# DC309A_FTDI.net
KiCad netlist of a schematic drawn in Altium Designer
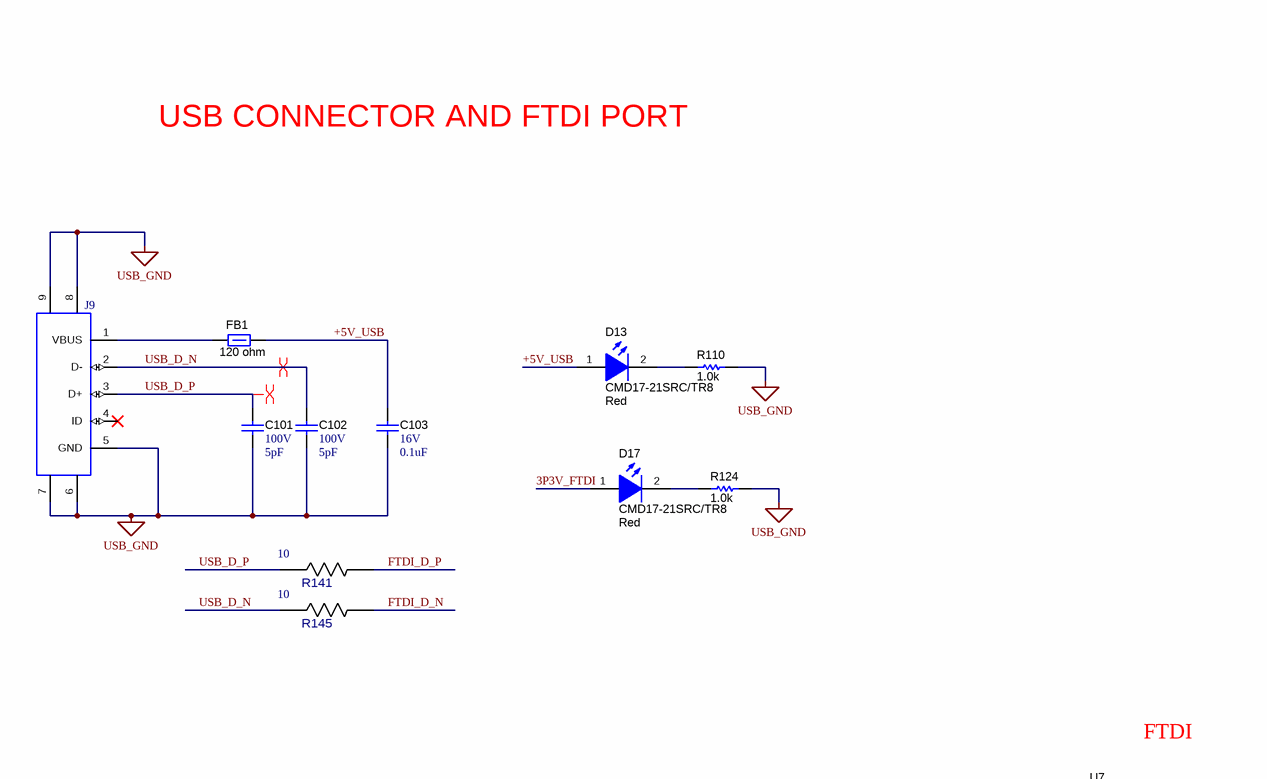
[diagram p0: DC309A_FTDI.SchDoc, top left]
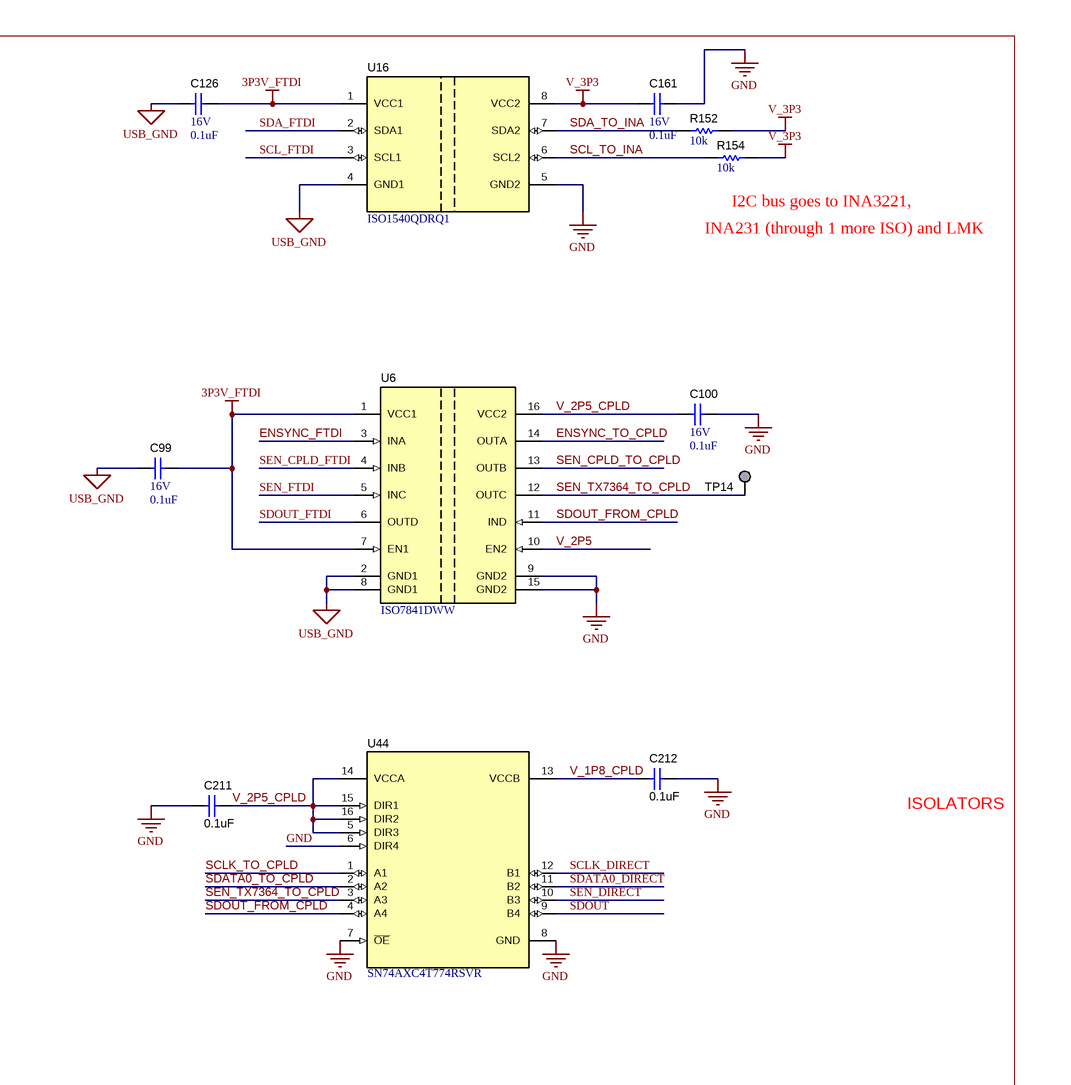
[diagram p1: DC309A_FTDI.SchDoc, top right]
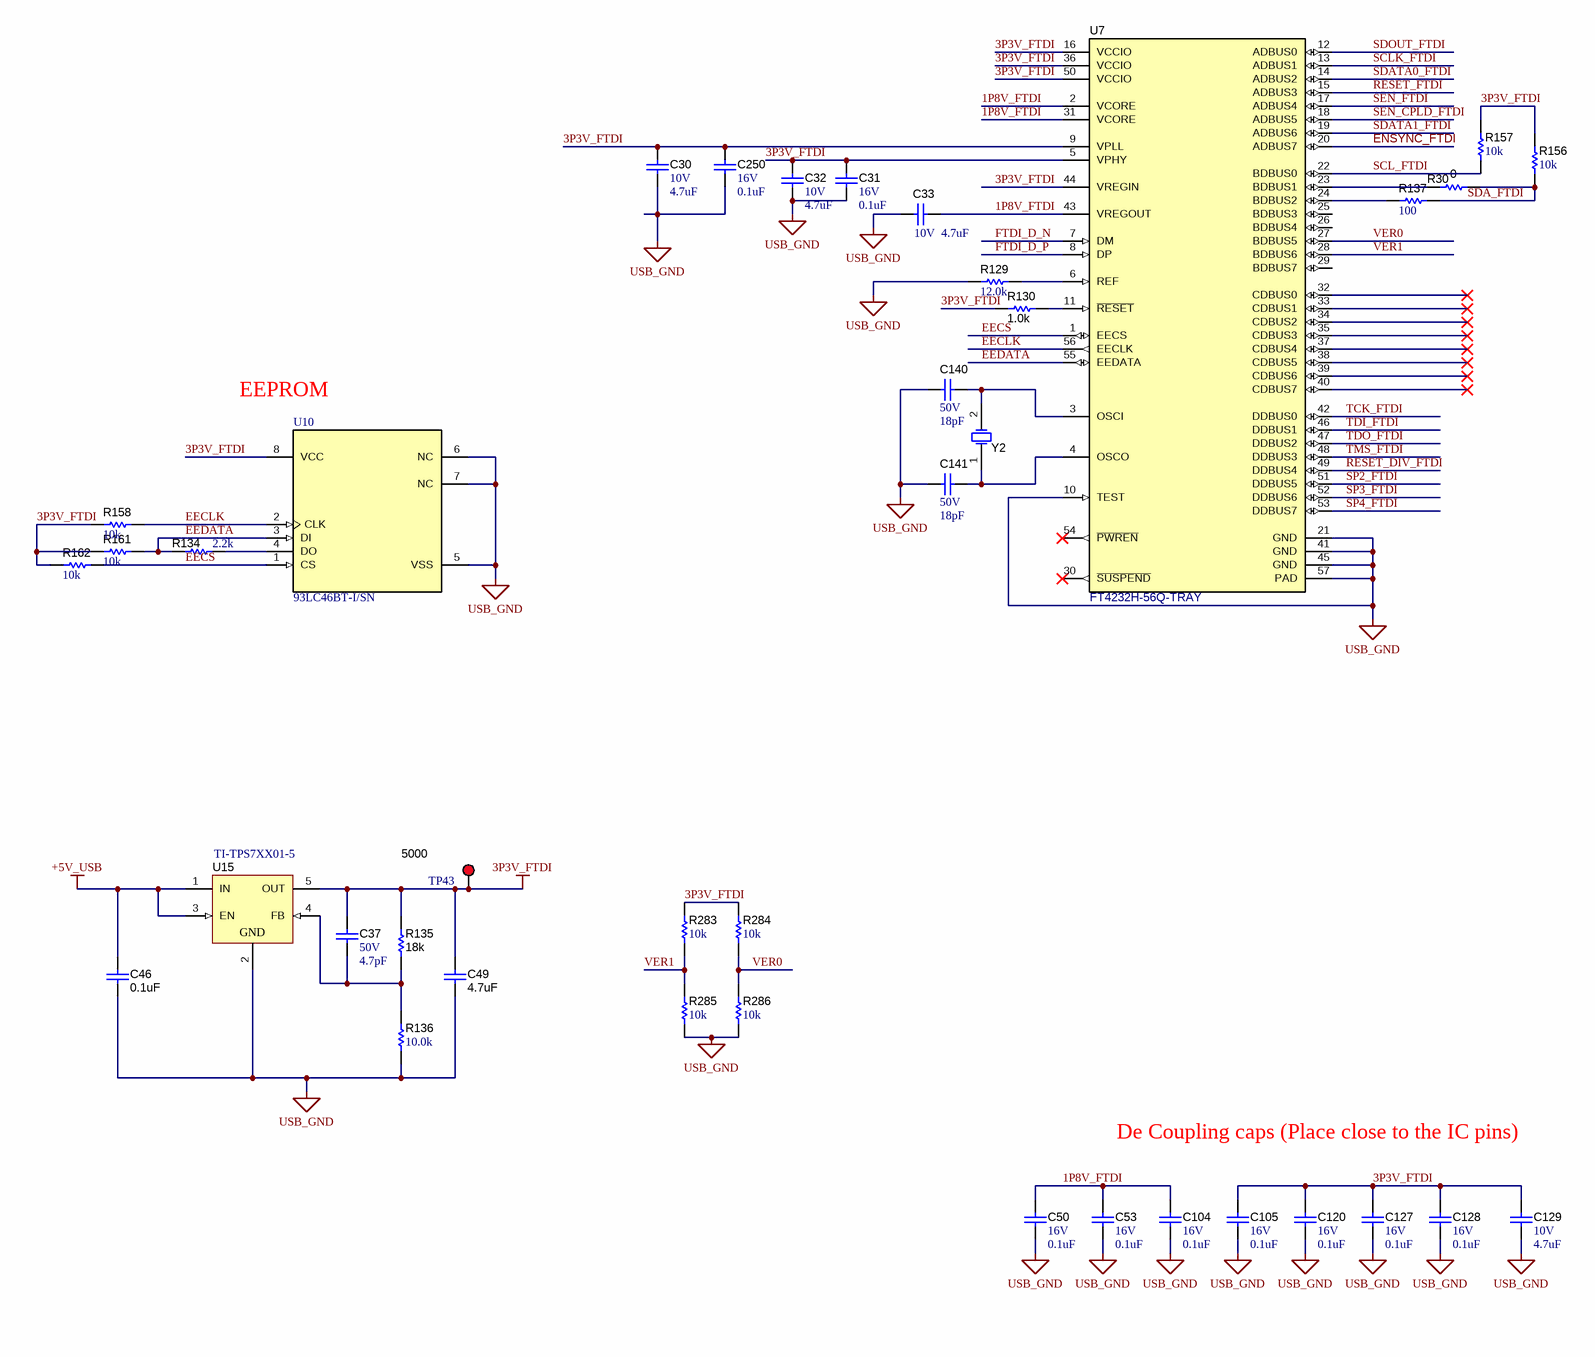
[diagram p2: DC309A_FTDI.SchDoc, bottom left]
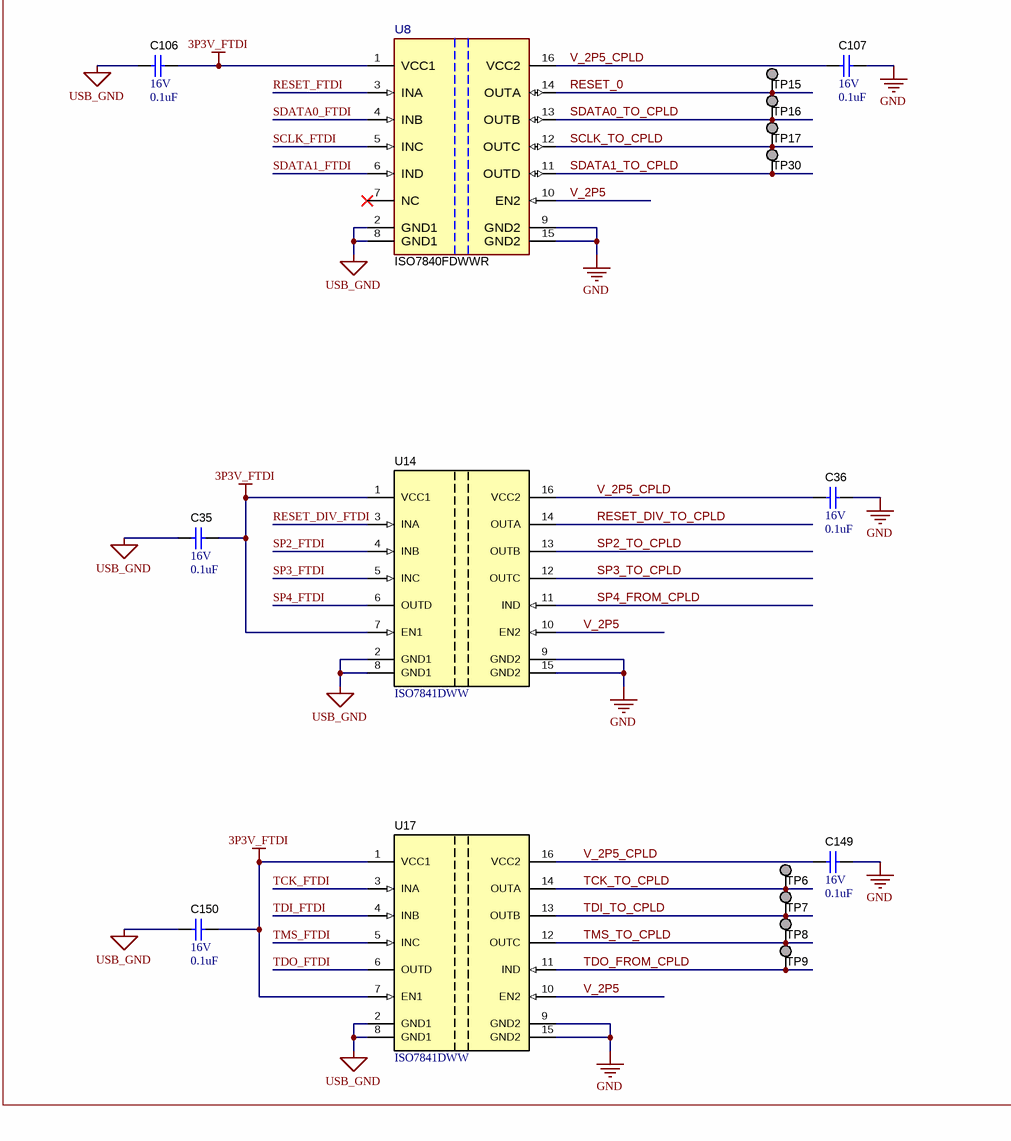
[diagram p3: DC309A_FTDI.SchDoc, bottom right]

(export (version "E")
  (design (tool "Eeschema 10.0.6"))
  (components
    (comp (ref "C30")
      (value "CL05A475MP5NRNC")
      (footprint "0402")
      (description "CAP, CERM, 4.7 uF, 10 V, +/- 20%, X5R, 0402")
      (fields
        (field (name "MANUFACTURER") "Samsung Electro-Mechanics")
        (field (name "VDC_V") "10V")
        (field (name "VALUEDISPLAYED") "4.7uF")
        (field (name "PUBLISHER") "Texas Instruments")
      )
      (libsource (lib "Altium Vault - TI") (part "Capacitor"))
    )
    (comp (ref "C31")
      (value "0402YC104KAT2A")
      (footprint "0402")
      (description "CAP, CERM, 0.1 uF, 16 V, +/- 10%, X7R, 0402")
      (fields
        (field (name "MANUFACTURER") "AVX")
        (field (name "VDC_V") "16V")
        (field (name "VALUEDISPLAYED") "0.1uF")
        (field (name "PUBLISHER") "Texas Instruments")
      )
      (libsource (lib "Altium Vault - TI") (part "Capacitor"))
    )
    (comp (ref "C32")
      (value "CL05A475MP5NRNC")
      (footprint "0402")
      (description "CAP, CERM, 4.7 uF, 10 V, +/- 20%, X5R, 0402")
      (fields
        (field (name "MANUFACTURER") "Samsung Electro-Mechanics")
        (field (name "VDC_V") "10V")
        (field (name "VALUEDISPLAYED") "4.7uF")
        (field (name "PUBLISHER") "Texas Instruments")
      )
      (libsource (lib "Altium Vault - TI") (part "Capacitor"))
    )
    (comp (ref "C33")
      (value "CL05A475MP5NRNC")
      (footprint "0402")
      (description "CAP, CERM, 4.7 uF, 10 V, +/- 20%, X5R, 0402")
      (fields
        (field (name "MANUFACTURER") "Samsung Electro-Mechanics")
        (field (name "VDC_V") "10V")
        (field (name "VALUEDISPLAYED") "4.7uF")
        (field (name "PUBLISHER") "Texas Instruments")
      )
      (libsource (lib "Altium Vault - TI") (part "Capacitor"))
    )
    (comp (ref "C35")
      (value "0402YC104KAT2A")
      (footprint "0402")
      (description "CAP, CERM, 0.1 uF, 16 V, +/- 10%, X7R, 0402")
      (fields
        (field (name "MANUFACTURER") "AVX")
        (field (name "VDC_V") "16V")
        (field (name "VALUEDISPLAYED") "0.1uF")
        (field (name "PUBLISHER") "Texas Instruments")
      )
      (libsource (lib "Altium Vault - TI") (part "Capacitor"))
    )
    (comp (ref "C36")
      (value "0402YC104KAT2A")
      (footprint "0402")
      (description "CAP, CERM, 0.1 uF, 16 V, +/- 10%, X7R, 0402")
      (fields
        (field (name "MANUFACTURER") "AVX")
        (field (name "VDC_V") "16V")
        (field (name "VALUEDISPLAYED") "0.1uF")
        (field (name "PUBLISHER") "Texas Instruments")
      )
      (libsource (lib "Altium Vault - TI") (part "Capacitor"))
    )
    (comp (ref "C37")
      (value "06035A4R7CAT2A")
      (footprint "0603")
      (description "CAP, CERM, 4.7 pF, 50 V, +/- 5%, C0G/NP0, 0603")
      (fields
        (field (name "MANUFACTURER") "AVX")
        (field (name "VDC_V") "50V")
        (field (name "VALUEDISPLAYED") "4.7pF")
        (field (name "PUBLISHER") "Texas Instruments")
      )
      (libsource (lib "Altium Vault - TI") (part "Capacitor"))
    )
    (comp (ref "C46")
      (value "Capacitor")
      (footprint "0402")
      (description "CAP, CERM, 0.1 uF, 16 V, +/- 10%, X7R, 0402")
      (fields
        (field (name "PARTNUMBER") "0402YC104KAT2A")
        (field (name "VALUEDISPLAYED") "0.1uF")
        (field (name "MANUFACTURER") "AVX")
        (field (name "PUBLISHER") "Texas Instruments")
      )
      (libsource (lib "Altium Vault - TI") (part "Capacitor"))
    )
    (comp (ref "C49")
      (value "Capacitor")
      (footprint "0805_HV")
      (description "CAP, CERM, 4.7 uF, 25 V, +/- 10%, X5R, 0805")
      (fields
        (field (name "PARTNUMBER") "C0805C475K3PACTU")
        (field (name "VALUEDISPLAYED") "4.7uF")
        (field (name "MANUFACTURER") "Kemet")
        (field (name "PUBLISHER") "Texas Instruments")
      )
      (libsource (lib "Altium Vault - TI") (part "CMP-0007800-2"))
    )
    (comp (ref "C50")
      (value "0402YC104KAT2A")
      (footprint "0402")
      (description "CAP, CERM, 0.1 uF, 16 V, +/- 10%, X7R, 0402")
      (fields
        (field (name "MANUFACTURER") "AVX")
        (field (name "VDC_V") "16V")
        (field (name "VALUEDISPLAYED") "0.1uF")
        (field (name "PUBLISHER") "Texas Instruments")
      )
      (libsource (lib "Altium Vault - TI") (part "Capacitor"))
    )
    (comp (ref "C53")
      (value "0402YC104KAT2A")
      (footprint "0402")
      (description "CAP, CERM, 0.1 uF, 16 V, +/- 10%, X7R, 0402")
      (fields
        (field (name "MANUFACTURER") "AVX")
        (field (name "VDC_V") "16V")
        (field (name "VALUEDISPLAYED") "0.1uF")
        (field (name "PUBLISHER") "Texas Instruments")
      )
      (libsource (lib "Altium Vault - TI") (part "Capacitor"))
    )
    (comp (ref "C99")
      (value "0402YC104KAT2A")
      (footprint "0402")
      (description "CAP, CERM, 0.1 uF, 16 V, +/- 10%, X7R, 0402")
      (fields
        (field (name "MANUFACTURER") "AVX")
        (field (name "VDC_V") "16V")
        (field (name "VALUEDISPLAYED") "0.1uF")
        (field (name "PUBLISHER") "Texas Instruments")
      )
      (libsource (lib "Altium Vault - TI") (part "Capacitor"))
    )
    (comp (ref "C100")
      (value "0402YC104KAT2A")
      (footprint "0402")
      (description "CAP, CERM, 0.1 uF, 16 V, +/- 10%, X7R, 0402")
      (fields
        (field (name "MANUFACTURER") "AVX")
        (field (name "VDC_V") "16V")
        (field (name "VALUEDISPLAYED") "0.1uF")
        (field (name "PUBLISHER") "Texas Instruments")
      )
      (libsource (lib "Altium Vault - TI") (part "Capacitor"))
    )
    (comp (ref "C101")
      (value "CBR04C509B1GAC")
      (footprint "0402")
      (description "CAP, CERM, 5 pF, 100 V,+/- 2%, C0G/NP0, 0402")
      (fields
        (field (name "MANUFACTURER") "Kemet")
        (field (name "VDC_V") "100V")
        (field (name "VALUEDISPLAYED") "5pF")
      )
      (libsource (lib "Altium Vault - TI") (part "Capacitor"))
    )
    (comp (ref "C102")
      (value "CBR04C509B1GAC")
      (footprint "0402")
      (description "CAP, CERM, 5 pF, 100 V,+/- 2%, C0G/NP0, 0402")
      (fields
        (field (name "MANUFACTURER") "Kemet")
        (field (name "VDC_V") "100V")
        (field (name "VALUEDISPLAYED") "5pF")
      )
      (libsource (lib "Altium Vault - TI") (part "Capacitor"))
    )
    (comp (ref "C103")
      (value "0402YC104KAT2A")
      (footprint "0402")
      (description "CAP, CERM, 0.1 uF, 16 V, +/- 10%, X7R, 0402")
      (fields
        (field (name "MANUFACTURER") "AVX")
        (field (name "VDC_V") "16V")
        (field (name "VALUEDISPLAYED") "0.1uF")
        (field (name "PUBLISHER") "Texas Instruments")
      )
      (libsource (lib "Altium Vault - TI") (part "Capacitor"))
    )
    (comp (ref "C104")
      (value "0402YC104KAT2A")
      (footprint "0402")
      (description "CAP, CERM, 0.1 uF, 16 V, +/- 10%, X7R, 0402")
      (fields
        (field (name "MANUFACTURER") "AVX")
        (field (name "VDC_V") "16V")
        (field (name "VALUEDISPLAYED") "0.1uF")
        (field (name "PUBLISHER") "Texas Instruments")
      )
      (libsource (lib "Altium Vault - TI") (part "Capacitor"))
    )
    (comp (ref "C105")
      (value "0402YC104KAT2A")
      (footprint "0402")
      (description "CAP, CERM, 0.1 uF, 16 V, +/- 10%, X7R, 0402")
      (fields
        (field (name "MANUFACTURER") "AVX")
        (field (name "VDC_V") "16V")
        (field (name "VALUEDISPLAYED") "0.1uF")
        (field (name "PUBLISHER") "Texas Instruments")
      )
      (libsource (lib "Altium Vault - TI") (part "Capacitor"))
    )
    (comp (ref "C106")
      (value "0402YC104KAT2A")
      (footprint "0402")
      (description "CAP, CERM, 0.1 uF, 16 V, +/- 10%, X7R, 0402")
      (fields
        (field (name "MANUFACTURER") "AVX")
        (field (name "VDC_V") "16V")
        (field (name "VALUEDISPLAYED") "0.1uF")
        (field (name "PUBLISHER") "Texas Instruments")
      )
      (libsource (lib "Altium Vault - TI") (part "Capacitor"))
    )
    (comp (ref "C107")
      (value "0402YC104KAT2A")
      (footprint "0402")
      (description "CAP, CERM, 0.1 uF, 16 V, +/- 10%, X7R, 0402")
      (fields
        (field (name "MANUFACTURER") "AVX")
        (field (name "VDC_V") "16V")
        (field (name "VALUEDISPLAYED") "0.1uF")
        (field (name "PUBLISHER") "Texas Instruments")
      )
      (libsource (lib "Altium Vault - TI") (part "Capacitor"))
    )
    (comp (ref "C120")
      (value "0402YC104KAT2A")
      (footprint "0402")
      (description "CAP, CERM, 0.1 uF, 16 V, +/- 10%, X7R, 0402")
      (fields
        (field (name "MANUFACTURER") "AVX")
        (field (name "VDC_V") "16V")
        (field (name "VALUEDISPLAYED") "0.1uF")
        (field (name "PUBLISHER") "Texas Instruments")
      )
      (libsource (lib "Altium Vault - TI") (part "Capacitor"))
    )
    (comp (ref "C126")
      (value "0402YC104KAT2A")
      (footprint "0402")
      (description "CAP, CERM, 0.1 uF, 16 V, +/- 10%, X7R, 0402")
      (fields
        (field (name "MANUFACTURER") "AVX")
        (field (name "VDC_V") "16V")
        (field (name "VALUEDISPLAYED") "0.1uF")
        (field (name "PUBLISHER") "Texas Instruments")
      )
      (libsource (lib "Altium Vault - TI") (part "Capacitor"))
    )
    (comp (ref "C127")
      (value "0402YC104KAT2A")
      (footprint "0402")
      (description "CAP, CERM, 0.1 uF, 16 V, +/- 10%, X7R, 0402")
      (fields
        (field (name "MANUFACTURER") "AVX")
        (field (name "VDC_V") "16V")
        (field (name "VALUEDISPLAYED") "0.1uF")
        (field (name "PUBLISHER") "Texas Instruments")
      )
      (libsource (lib "Altium Vault - TI") (part "Capacitor"))
    )
    (comp (ref "C128")
      (value "0402YC104KAT2A")
      (footprint "0402")
      (description "CAP, CERM, 0.1 uF, 16 V, +/- 10%, X7R, 0402")
      (fields
        (field (name "MANUFACTURER") "AVX")
        (field (name "VDC_V") "16V")
        (field (name "VALUEDISPLAYED") "0.1uF")
        (field (name "PUBLISHER") "Texas Instruments")
      )
      (libsource (lib "Altium Vault - TI") (part "Capacitor"))
    )
    (comp (ref "C129")
      (value "CL05A475MP5NRNC")
      (footprint "0402")
      (description "CAP, CERM, 4.7 uF, 10 V, +/- 20%, X5R, 0402")
      (fields
        (field (name "MANUFACTURER") "Samsung Electro-Mechanics")
        (field (name "VDC_V") "10V")
        (field (name "VALUEDISPLAYED") "4.7uF")
        (field (name "PUBLISHER") "Texas Instruments")
      )
      (libsource (lib "Altium Vault - TI") (part "Capacitor"))
    )
    (comp (ref "C140")
      (value "06035A180JAT2A")
      (footprint "0603")
      (description "CAP, CERM, 18 pF, 50 V, +/- 5%, C0G/NP0, 0603")
      (fields
        (field (name "MANUFACTURER") "AVX")
        (field (name "VDC_V") "50V")
        (field (name "VALUEDISPLAYED") "18pF")
        (field (name "PUBLISHER") "Texas Instruments")
      )
      (libsource (lib "Altium Vault - TI") (part "Capacitor"))
    )
    (comp (ref "C141")
      (value "06035A180JAT2A")
      (footprint "0603")
      (description "CAP, CERM, 18 pF, 50 V, +/- 5%, C0G/NP0, 0603")
      (fields
        (field (name "MANUFACTURER") "AVX")
        (field (name "VDC_V") "50V")
        (field (name "VALUEDISPLAYED") "18pF")
        (field (name "PUBLISHER") "Texas Instruments")
      )
      (libsource (lib "Altium Vault - TI") (part "Capacitor"))
    )
    (comp (ref "C149")
      (value "0402YC104KAT2A")
      (footprint "0402")
      (description "CAP, CERM, 0.1 uF, 16 V, +/- 10%, X7R, 0402")
      (fields
        (field (name "MANUFACTURER") "AVX")
        (field (name "VDC_V") "16V")
        (field (name "VALUEDISPLAYED") "0.1uF")
        (field (name "PUBLISHER") "Texas Instruments")
      )
      (libsource (lib "Altium Vault - TI") (part "Capacitor"))
    )
    (comp (ref "C150")
      (value "0402YC104KAT2A")
      (footprint "0402")
      (description "CAP, CERM, 0.1 uF, 16 V, +/- 10%, X7R, 0402")
      (fields
        (field (name "MANUFACTURER") "AVX")
        (field (name "VDC_V") "16V")
        (field (name "VALUEDISPLAYED") "0.1uF")
        (field (name "PUBLISHER") "Texas Instruments")
      )
      (libsource (lib "Altium Vault - TI") (part "Capacitor"))
    )
    (comp (ref "C161")
      (value "0402YC104KAT2A")
      (footprint "0402")
      (description "CAP, CERM, 0.1 uF, 16 V, +/- 10%, X7R, 0402")
      (fields
        (field (name "MANUFACTURER") "AVX")
        (field (name "VDC_V") "16V")
        (field (name "VALUEDISPLAYED") "0.1uF")
        (field (name "PUBLISHER") "Texas Instruments")
      )
      (libsource (lib "Altium Vault - TI") (part "Capacitor"))
    )
    (comp (ref "C211")
      (value "0.1uF")
      (footprint "0402")
      (description "CAP, CERM, 0.1 uF, 16 V, +/- 10%, X7R, 0402")
      (fields
        (field (name "PARTNUMBER") "GRM155R71C104KA88D")
        (field (name "MANUFACTURER") "MuRata")
        (field (name "PUBLISHER") "Texas Instruments")
      )
      (libsource (lib "Altium Vault - TI") (part "Capacitor"))
    )
    (comp (ref "C212")
      (value "0.1uF")
      (footprint "0402")
      (description "CAP, CERM, 0.1 uF, 16 V, +/- 10%, X7R, 0402")
      (fields
        (field (name "PARTNUMBER") "GRM155R71C104KA88D")
        (field (name "MANUFACTURER") "MuRata")
        (field (name "PUBLISHER") "Texas Instruments")
      )
      (libsource (lib "Altium Vault - TI") (part "Capacitor"))
    )
    (comp (ref "C250")
      (value "0402YC104KAT2A")
      (footprint "0402")
      (description "CAP, CERM, 0.1 uF, 16 V, +/- 10%, X7R, 0402")
      (fields
        (field (name "MANUFACTURER") "AVX")
        (field (name "VDC_V") "16V")
        (field (name "VALUEDISPLAYED") "0.1uF")
        (field (name "PUBLISHER") "Texas Instruments")
      )
      (libsource (lib "Altium Vault - TI") (part "Capacitor"))
    )
    (comp (ref "D13")
      (value "CMD17-21SRC/TR8")
      (footprint "CMD17-21_Red")
      (description "LED, Red, SMD")
      (fields
        (field (name "ALTIUM_VALUE") "Red")
        (field (name "MANUFACTURER") "Visual Communications Company, LLC")
      )
      (libsource (lib "Altium Vault - TI") (part "LED"))
    )
    (comp (ref "D17")
      (value "CMD17-21SRC/TR8")
      (footprint "CMD17-21_Red")
      (description "LED, Red, SMD")
      (fields
        (field (name "ALTIUM_VALUE") "Red")
        (field (name "MANUFACTURER") "Visual Communications Company, LLC")
      )
      (libsource (lib "Altium Vault - TI") (part "LED"))
    )
    (comp (ref "FB1")
      (value "120 ohm")
      (footprint "0603")
      (description "Ferrite Bead, 120 ohm @ 100 MHz, 3 A, 0603")
      (fields
        (field (name "PARTNUMBER") "BLM18SG121TN1D")
        (field (name "MANUFACTURER") "MuRata")
        (field (name "PUBLISHER") "Texas Instruments")
      )
      (libsource (lib "Altium Vault - TI") (part "Ferrite_Bead"))
    )
    (comp (ref "J9")
      (value "CONN_USB_MINI-AB_4Shld")
      (footprint "Molex_67803-8020")
      (description "Connector, Receptacle, USB - mini AB, R/A, SMD")
      (fields
        (field (name "PARTNUMBER") "67803-8020")
        (field (name "MANUFACTURER") "Molex")
        (field (name "PUBLISHER") "Texas Instruments")
      )
      (libsource (lib "Altium Vault - TI") (part "CONN_USB_MINI-AB_4Shld"))
    )
    (comp (ref "R30")
      (value "0")
      (footprint "0402")
      (description "RES, 0, 5%, 0.1 W, AEC-Q200 Grade 0, 0402")
      (fields (field (name "PARTNUMBER") "ERJ-2GE0R00X") (field (name "MANUFACTURER") "Panasonic"))
      (libsource (lib "Altium Vault - TI") (part "CMP-0026992-3"))
    )
    (comp (ref "R110")
      (value "Resistor")
      (footprint "0402")
      (description "RES, 1.0 k, 5%, 0.063 W, AEC-Q200 Grade 0, 0402")
      (fields
        (field (name "PARTNUMBER") "CRCW04021K00JNED")
        (field (name "VALUEDISPLAYED") "1.0k")
        (field (name "MANUFACTURER") "Vishay-Dale")
      )
      (libsource (lib "Altium Vault - TI") (part "Resistor"))
    )
    (comp (ref "R124")
      (value "Resistor")
      (footprint "0402")
      (description "RES, 1.0 k, 5%, 0.063 W, AEC-Q200 Grade 0, 0402")
      (fields
        (field (name "PARTNUMBER") "CRCW04021K00JNED")
        (field (name "VALUEDISPLAYED") "1.0k")
        (field (name "MANUFACTURER") "Vishay-Dale")
      )
      (libsource (lib "Altium Vault - TI") (part "Resistor"))
    )
    (comp (ref "R129")
      (value "CRCW040212K0FKED")
      (footprint "0402")
      (description "RES, 12.0 k, 1%, 0.063 W, AEC-Q200 Grade 0, 0402")
      (fields (field (name "MANUFACTURER") "Vishay-Dale") (field (name "VALUEDISPLAYED") "12.0k"))
      (libsource (lib "Altium Vault - TI") (part "Resistor"))
    )
    (comp (ref "R130")
      (value "Resistor")
      (footprint "0402")
      (description "RES, 1.0 k, 5%, 0.063 W, AEC-Q200 Grade 0, 0402")
      (fields
        (field (name "PARTNUMBER") "CRCW04021K00JNED")
        (field (name "VALUEDISPLAYED") "1.0k")
        (field (name "MANUFACTURER") "Vishay-Dale")
      )
      (libsource (lib "Altium Vault - TI") (part "Resistor"))
    )
    (comp (ref "R134")
      (value "CRCW04022K20JNED")
      (footprint "0402")
      (description "RES, 2.2 k, 5%, 0.063 W, AEC-Q200 Grade 0, 0402")
      (fields (field (name "MANUFACTURER") "Vishay-Dale") (field (name "VALUEDISPLAYED") "2.2k"))
      (libsource (lib "Altium Vault - TI") (part "Resistor"))
    )
    (comp (ref "R135")
      (value "CRCW040218K0JNED")
      (footprint "0402")
      (description "RES, 18 k, 5%, 0.063 W, AEC-Q200 Grade 0, 0402")
      (fields (field (name "MANUFACTURER") "Vishay-Dale") (field (name "VALUEDISPLAYED") "18k"))
      (libsource (lib "Altium Vault - TI") (part "CMP-0026850-3"))
    )
    (comp (ref "R136")
      (value "CRCW040210K0DHEDP")
      (footprint "0402")
      (description "RES, 10.0 k, 0.5%, 0.063 W, AEC-Q200 Grade 0, 0402")
      (fields (field (name "MANUFACTURER") "Vishay-Dale") (field (name "VALUEDISPLAYED") "10.0k"))
      (libsource (lib "Altium Vault - TI") (part "Resistor"))
    )
    (comp (ref "R137")
      (value "CRCW0402100RFKED")
      (footprint "0402")
      (description "RES, 100, 1%, 0.063 W, AEC-Q200 Grade 0, 0402")
      (fields (field (name "MANUFACTURER") "Vishay-Dale") (field (name "VALUEDISPLAYED") "100"))
      (libsource (lib "Altium Vault - TI") (part "Resistor"))
    )
    (comp (ref "R141")
      (value "ERJ-3GEYJ100V")
      (footprint "FP-ERJ-3GEYJ100V_0603-MFG")
      (description "Thick Film Resistors - SMD 0603 10ohms 5% AEC-Q200")
      (fields (field (name "MANUFACTURER") "Panasonic") (field (name "RES_OHM") "10"))
      (libsource (lib "Altium Vault - TI") (part "SYM-PMR18EZPJ000"))
    )
    (comp (ref "R145")
      (value "ERJ-3GEYJ100V")
      (footprint "FP-ERJ-3GEYJ100V_0603-MFG")
      (description "Thick Film Resistors - SMD 0603 10ohms 5% AEC-Q200")
      (fields (field (name "MANUFACTURER") "Panasonic") (field (name "RES_OHM") "10"))
      (libsource (lib "Altium Vault - TI") (part "SYM-PMR18EZPJ000"))
    )
    (comp (ref "R152")
      (value "ERJ-2GEJ103X")
      (footprint "0402")
      (description "RES, 10 k, 5%, 0.1 W, AEC-Q200 Grade 0, 0402")
      (fields
        (field (name "MANUFACTURER") "Panasonic")
        (field (name "VALUEDISPLAYED") "10k")
        (field (name "PUBLISHER") "Texas Instruments")
      )
      (libsource (lib "Altium Vault - TI") (part "Resistor"))
    )
    (comp (ref "R154")
      (value "ERJ-2GEJ103X")
      (footprint "0402")
      (description "RES, 10 k, 5%, 0.1 W, AEC-Q200 Grade 0, 0402")
      (fields
        (field (name "MANUFACTURER") "Panasonic")
        (field (name "VALUEDISPLAYED") "10k")
        (field (name "PUBLISHER") "Texas Instruments")
      )
      (libsource (lib "Altium Vault - TI") (part "Resistor"))
    )
    (comp (ref "R156")
      (value "ERJ-2GEJ103X")
      (footprint "0402")
      (description "RES, 10 k, 5%, 0.1 W, AEC-Q200 Grade 0, 0402")
      (fields
        (field (name "MANUFACTURER") "Panasonic")
        (field (name "VALUEDISPLAYED") "10k")
        (field (name "PUBLISHER") "Texas Instruments")
      )
      (libsource (lib "Altium Vault - TI") (part "Resistor"))
    )
    (comp (ref "R157")
      (value "ERJ-2GEJ103X")
      (footprint "0402")
      (description "RES, 10 k, 5%, 0.1 W, AEC-Q200 Grade 0, 0402")
      (fields
        (field (name "MANUFACTURER") "Panasonic")
        (field (name "VALUEDISPLAYED") "10k")
        (field (name "PUBLISHER") "Texas Instruments")
      )
      (libsource (lib "Altium Vault - TI") (part "Resistor"))
    )
    (comp (ref "R158")
      (value "ERJ-2GEJ103X")
      (footprint "0402")
      (description "RES, 10 k, 5%, 0.1 W, AEC-Q200 Grade 0, 0402")
      (fields
        (field (name "MANUFACTURER") "Panasonic")
        (field (name "VALUEDISPLAYED") "10k")
        (field (name "PUBLISHER") "Texas Instruments")
      )
      (libsource (lib "Altium Vault - TI") (part "Resistor"))
    )
    (comp (ref "R161")
      (value "ERJ-2GEJ103X")
      (footprint "0402")
      (description "RES, 10 k, 5%, 0.1 W, AEC-Q200 Grade 0, 0402")
      (fields
        (field (name "MANUFACTURER") "Panasonic")
        (field (name "VALUEDISPLAYED") "10k")
        (field (name "PUBLISHER") "Texas Instruments")
      )
      (libsource (lib "Altium Vault - TI") (part "Resistor"))
    )
    (comp (ref "R162")
      (value "ERJ-2GEJ103X")
      (footprint "0402")
      (description "RES, 10 k, 5%, 0.1 W, AEC-Q200 Grade 0, 0402")
      (fields
        (field (name "MANUFACTURER") "Panasonic")
        (field (name "VALUEDISPLAYED") "10k")
        (field (name "PUBLISHER") "Texas Instruments")
      )
      (libsource (lib "Altium Vault - TI") (part "Resistor"))
    )
    (comp (ref "R283")
      (value "ERJ-2GEJ103X")
      (footprint "0402")
      (description "RES, 10 k, 5%, 0.1 W, AEC-Q200 Grade 0, 0402")
      (fields
        (field (name "MANUFACTURER") "Panasonic")
        (field (name "VALUEDISPLAYED") "10k")
        (field (name "PUBLISHER") "Texas Instruments")
      )
      (libsource (lib "Altium Vault - TI") (part "Resistor"))
    )
    (comp (ref "R284")
      (value "ERJ-2GEJ103X")
      (footprint "0402")
      (description "RES, 10 k, 5%, 0.1 W, AEC-Q200 Grade 0, 0402")
      (fields
        (field (name "MANUFACTURER") "Panasonic")
        (field (name "VALUEDISPLAYED") "10k")
        (field (name "PUBLISHER") "Texas Instruments")
      )
      (libsource (lib "Altium Vault - TI") (part "Resistor"))
    )
    (comp (ref "R285")
      (value "ERJ-2GEJ103X")
      (footprint "0402")
      (description "RES, 10 k, 5%, 0.1 W, AEC-Q200 Grade 0, 0402")
      (fields
        (field (name "MANUFACTURER") "Panasonic")
        (field (name "VALUEDISPLAYED") "10k")
        (field (name "PUBLISHER") "Texas Instruments")
      )
      (libsource (lib "Altium Vault - TI") (part "Resistor"))
    )
    (comp (ref "R286")
      (value "ERJ-2GEJ103X")
      (footprint "0402")
      (description "RES, 10 k, 5%, 0.1 W, AEC-Q200 Grade 0, 0402")
      (fields
        (field (name "MANUFACTURER") "Panasonic")
        (field (name "VALUEDISPLAYED") "10k")
        (field (name "PUBLISHER") "Texas Instruments")
      )
      (libsource (lib "Altium Vault - TI") (part "Resistor"))
    )
    (comp (ref "TP6")
      (value "~")
      (footprint "TP_50MIL-SMT")
      (description "TEST POINT.  No entry in BOM.")
      (libsource (lib "Altium Vault - TI") (part "TESTPOINT"))
    )
    (comp (ref "TP7")
      (value "~")
      (footprint "TP_50MIL-SMT")
      (description "TEST POINT.  No entry in BOM.")
      (libsource (lib "Altium Vault - TI") (part "TESTPOINT"))
    )
    (comp (ref "TP8")
      (value "~")
      (footprint "TP_50MIL-SMT")
      (description "TEST POINT.  No entry in BOM.")
      (libsource (lib "Altium Vault - TI") (part "TESTPOINT"))
    )
    (comp (ref "TP9")
      (value "~")
      (footprint "TP_50MIL-SMT")
      (description "TEST POINT.  No entry in BOM.")
      (libsource (lib "Altium Vault - TI") (part "TESTPOINT"))
    )
    (comp (ref "TP14")
      (value "~")
      (footprint "TP_50MIL-SMT")
      (description "TEST POINT.  No entry in BOM.")
      (libsource (lib "Altium Vault - TI") (part "TESTPOINT"))
    )
    (comp (ref "TP15")
      (value "~")
      (footprint "TP_50MIL-SMT")
      (description "TEST POINT.  No entry in BOM.")
      (libsource (lib "Altium Vault - TI") (part "TESTPOINT"))
    )
    (comp (ref "TP16")
      (value "~")
      (footprint "TP_50MIL-SMT")
      (description "TEST POINT.  No entry in BOM.")
      (libsource (lib "Altium Vault - TI") (part "TESTPOINT"))
    )
    (comp (ref "TP17")
      (value "~")
      (footprint "TP_50MIL-SMT")
      (description "TEST POINT.  No entry in BOM.")
      (libsource (lib "Altium Vault - TI") (part "TESTPOINT"))
    )
    (comp (ref "TP30")
      (value "~")
      (footprint "TP_50MIL-SMT")
      (description "TEST POINT.  No entry in BOM.")
      (libsource (lib "Altium Vault - TI") (part "TESTPOINT"))
    )
    (comp (ref "TP43")
      (value "5000")
      (footprint "Keystone5000")
      (description "Test Point, Miniature, Red, TH")
      (fields
        (field (name "MANUFACTURER") "Keystone Electronics")
        (field (name "PUBLISHER") "Texas Instruments")
      )
      (libsource (lib "Altium Vault - TI") (part "5000"))
    )
    (comp (ref "U6")
      (value "ISO7841DWW")
      (footprint "DWW0016A_L")
      (description "High-Immunity, 5.7kVRMS Reinforced Quad-Channel 3/1 Digital Isolator, 100Mbps, DWW0016A (SOIC-16)")
      (fields
        (field (name "PARTNUMBER") "ISO7841DWW")
        (field (name "MANUFACTURER") "Texas Instruments")
        (field (name "ALTERNATE PARTNUMBER") "ISO7841DWWR")
      )
      (libsource (lib "Altium Vault - TI") (part "ISO7841"))
    )
    (comp (ref "U7")
      (value "FT4232H-56Q-TRAY")
      (footprint "VQFN-56")
      (fields (field (name "MANUFACTURER") "FTDI"))
      (libsource (lib "Altium Vault - TI") (part "FT4232H-56Q"))
    )
    (comp (ref "U8")
      (value "ISO7840FDWWR")
      (footprint "DWW0016A-MFG")
      (description "High-Performance, 8000-VPK Reinforced Quad-Channel Digital Isolator")
      (fields
        (field (name "MANUFACTURER") "Texas Instruments")
        (field (name "PARTNUMBER") "ISO7840FDWWR")
        (field (name "DIGIKEY PART NUMBER") "296-45223-1-ND")
      )
      (libsource (lib "Altium Vault - TI") (part "SYM-ISO7840FDWWR"))
    )
    (comp (ref "U10")
      (value "93LC46BT-I/SN")
      (footprint "SOIC-8")
      (description "1K Microwire Compatible Serial EEPROM")
      (fields (field (name "MANUFACTURER") "Microchip") (field (name "PUBLISHER") "Texas Instruments"))
      (libsource (lib "Altium Vault - TI") (part "93LC46A_B-SN"))
    )
    (comp (ref "U14")
      (value "ISO7841DWW")
      (footprint "DWW0016A_L")
      (description "High-Immunity, 5.7kVRMS Reinforced Quad-Channel 3/1 Digital Isolator, 100Mbps, DWW0016A (SOIC-16)")
      (fields
        (field (name "PARTNUMBER") "ISO7841DWW")
        (field (name "MANUFACTURER") "Texas Instruments")
        (field (name "ALTERNATE PARTNUMBER") "ISO7841DWWR")
      )
      (libsource (lib "Altium Vault - TI") (part "ISO7841"))
    )
    (comp (ref "U15")
      (value "TI-TPS7XX01-5")
      (footprint "DDC0005A_N")
      (fields (field (name "MANUFACTURER") "Texas Instruments") (field (name "PARTNUMBER") "TPS79901DDCR"))
      (libsource (lib "Altium Vault - TI") (part "CMP-0035863-1"))
    )
    (comp (ref "U16")
      (value "ISO1540QDRQ1")
      (footprint "D0008B_L")
      (description "Low-Power Bidirectional I2C Isolators, D0008B (SOIC-8)")
      (fields
        (field (name "MANUFACTURER") "Texas Instruments")
        (field (name "ALTERNATE PARTNUMBER") "ISO1540QDQ1")
        (field (name "PARTNUMBER") "ISO1540QDRQ1")
      )
      (libsource (lib "Altium Vault - TI") (part "ISO1541"))
    )
    (comp (ref "U17")
      (value "ISO7841DWW")
      (footprint "DWW0016A_L")
      (description "High-Immunity, 5.7kVRMS Reinforced Quad-Channel 3/1 Digital Isolator, 100Mbps, DWW0016A (SOIC-16)")
      (fields
        (field (name "PARTNUMBER") "ISO7841DWW")
        (field (name "MANUFACTURER") "Texas Instruments")
        (field (name "ALTERNATE PARTNUMBER") "ISO7841DWWR")
      )
      (libsource (lib "Altium Vault - TI") (part "ISO7841"))
    )
    (comp (ref "U44")
      (value "SN74AXC4T774RSVR")
      (footprint "RSV0016A")
      (description "4 Bit Direction Controlled Level Translator, RSV0016A (UQFN-16)")
      (fields
        (field (name "MANUFACTURER") "Texas Instruments")
        (field (name "PARTNUMBER") "SN74AXC4T774RSVR")
      )
      (libsource (lib "Altium Vault - TI") (part "SN74AVC4T774RSV"))
    )
    (comp (ref "Y2")
      (value "ABM3-12.000MHZ-D2Y-T")
      (footprint "XTAL_ABM3")
      (description "Crystal, 12 MHz, 18 pF, SMD")
      (fields (field (name "MANUFACTURER") "Abracon Corporation"))
      (libsource (lib "Altium Vault - TI") (part "Xtal"))
    )
  )
  (nets
    (net (code "1") (name "+5V_USB") (class "Default")
      (node (ref "C103") (pin "1") (pinfunction "1_1") (pintype "passive"))
      (node (ref "C46") (pin "1") (pinfunction "1_1") (pintype "passive"))
      (node (ref "D13") (pin "1") (pinfunction "A_1") (pintype "passive"))
      (node (ref "FB1") (pin "2") (pinfunction "2_2") (pintype "passive"))
      (node (ref "U15") (pin "1") (pinfunction "IN_1") (pintype "power_in"))
      (node (ref "U15") (pin "3") (pinfunction "EN_3") (pintype "input"))
    )
    (net (code "2") (name "/1P8V_FTDI") (class "Default")
      (node (ref "C104") (pin "1") (pinfunction "1_1") (pintype "passive"))
      (node (ref "C33") (pin "2") (pinfunction "2_2") (pintype "passive"))
      (node (ref "C50") (pin "1") (pinfunction "1_1") (pintype "passive"))
      (node (ref "C53") (pin "1") (pinfunction "1_1") (pintype "passive"))
      (node (ref "U7") (pin "2") (pinfunction "VCORE_2") (pintype "power_in"))
      (node (ref "U7") (pin "31") (pinfunction "VCORE_31") (pintype "power_in"))
      (node (ref "U7") (pin "43") (pinfunction "VREGOUT_43") (pintype "power_in"))
    )
    (net (code "3") (name "/EECLK") (class "Default")
      (node (ref "R158") (pin "2") (pinfunction "2_2") (pintype "passive"))
      (node (ref "U10") (pin "2") (pinfunction "CLK_2") (pintype "input"))
      (node (ref "U7") (pin "56") (pinfunction "EECLK_56") (pintype "output"))
    )
    (net (code "4") (name "/EECS") (class "Default")
      (node (ref "R162") (pin "2") (pinfunction "2_2") (pintype "passive"))
      (node (ref "U10") (pin "1") (pinfunction "CS_1") (pintype "input"))
      (node (ref "U7") (pin "1") (pinfunction "EECS_1") (pintype "bidirectional"))
    )
    (net (code "5") (name "/EEDATA") (class "Default")
      (node (ref "R134") (pin "1") (pinfunction "1_1") (pintype "passive"))
      (node (ref "R161") (pin "2") (pinfunction "2_2") (pintype "passive"))
      (node (ref "U10") (pin "3") (pinfunction "DI_3") (pintype "input"))
      (node (ref "U7") (pin "55") (pinfunction "EEDATA_55") (pintype "bidirectional"))
    )
    (net (code "6") (name "/ENSYNC_FTDI") (class "Default")
      (node (ref "U6") (pin "3") (pinfunction "INA_3") (pintype "input"))
      (node (ref "U7") (pin "20") (pinfunction "ADBUS7_20") (pintype "bidirectional"))
    )
    (net (code "7") (name "/ENSYNC_TO_CPLD") (class "Default")
      (node (ref "U6") (pin "14") (pinfunction "OUTA_14") (pintype "tri_state"))
    )
    (net (code "8") (name "/FTDI_D_N") (class "Default")
      (node (ref "R145") (pin "2") (pinfunction "2_2") (pintype "passive"))
      (node (ref "U7") (pin "7") (pinfunction "DM_7") (pintype "input"))
    )
    (net (code "9") (name "/FTDI_D_P") (class "Default")
      (node (ref "R141") (pin "2") (pinfunction "2_2") (pintype "passive"))
      (node (ref "U7") (pin "8") (pinfunction "DP_8") (pintype "input"))
    )
    (net (code "10") (name "/RESET_0") (class "Default")
      (node (ref "TP15") (pin "1") (pintype "passive"))
      (node (ref "U8") (pin "14") (pinfunction "OUTA_14") (pintype "bidirectional"))
    )
    (net (code "11") (name "/RESET_DIV_FTDI") (class "Default")
      (node (ref "U14") (pin "3") (pinfunction "INA_3") (pintype "input"))
      (node (ref "U7") (pin "49") (pinfunction "DDBUS4_49") (pintype "bidirectional"))
    )
    (net (code "12") (name "/RESET_DIV_TO_CPLD") (class "Default")
      (node (ref "U14") (pin "14") (pinfunction "OUTA_14") (pintype "tri_state"))
    )
    (net (code "13") (name "/RESET_FTDI") (class "Default")
      (node (ref "U7") (pin "15") (pinfunction "ADBUS3_15") (pintype "bidirectional"))
      (node (ref "U8") (pin "3") (pinfunction "INA_3") (pintype "input"))
    )
    (net (code "14") (name "/SCLK_DIRECT") (class "Default")
      (node (ref "U44") (pin "12") (pinfunction "B1_12") (pintype "bidirectional"))
    )
    (net (code "15") (name "/SCLK_FTDI") (class "Default")
      (node (ref "U7") (pin "13") (pinfunction "ADBUS1_13") (pintype "bidirectional"))
      (node (ref "U8") (pin "5") (pinfunction "INC_5") (pintype "input"))
    )
    (net (code "16") (name "/SCLK_TO_CPLD") (class "Default")
      (node (ref "TP17") (pin "1") (pintype "passive"))
      (node (ref "U44") (pin "1") (pinfunction "A1_1") (pintype "bidirectional"))
      (node (ref "U8") (pin "12") (pinfunction "OUTC_12") (pintype "bidirectional"))
    )
    (net (code "17") (name "/SCL_FTDI") (class "Default")
      (node (ref "R157") (pin "2") (pinfunction "2_2") (pintype "passive"))
      (node (ref "U16") (pin "3") (pinfunction "SCL1_3") (pintype "bidirectional"))
      (node (ref "U7") (pin "22") (pinfunction "BDBUS0_22") (pintype "bidirectional"))
    )
    (net (code "18") (name "/SCL_TO_INA") (class "Default")
      (node (ref "R154") (pin "1") (pinfunction "1_1") (pintype "passive"))
      (node (ref "U16") (pin "6") (pinfunction "SCL2_6") (pintype "bidirectional"))
    )
    (net (code "19") (name "/SDATA0_DIRECT") (class "Default")
      (node (ref "U44") (pin "11") (pinfunction "B2_11") (pintype "bidirectional"))
    )
    (net (code "20") (name "/SDATA0_FTDI") (class "Default")
      (node (ref "U7") (pin "14") (pinfunction "ADBUS2_14") (pintype "bidirectional"))
      (node (ref "U8") (pin "4") (pinfunction "INB_4") (pintype "input"))
    )
    (net (code "21") (name "/SDATA0_TO_CPLD") (class "Default")
      (node (ref "TP16") (pin "1") (pintype "passive"))
      (node (ref "U44") (pin "2") (pinfunction "A2_2") (pintype "bidirectional"))
      (node (ref "U8") (pin "13") (pinfunction "OUTB_13") (pintype "bidirectional"))
    )
    (net (code "22") (name "/SDATA1_FTDI") (class "Default")
      (node (ref "U7") (pin "19") (pinfunction "ADBUS6_19") (pintype "bidirectional"))
      (node (ref "U8") (pin "6") (pinfunction "IND_6") (pintype "input"))
    )
    (net (code "23") (name "/SDATA1_TO_CPLD") (class "Default")
      (node (ref "TP30") (pin "1") (pintype "passive"))
      (node (ref "U8") (pin "11") (pinfunction "OUTD_11") (pintype "bidirectional"))
    )
    (net (code "24") (name "/SDA_FTDI") (class "Default")
      (node (ref "R137") (pin "2") (pinfunction "2_2") (pintype "passive"))
      (node (ref "R156") (pin "2") (pinfunction "2_2") (pintype "passive"))
      (node (ref "R30") (pin "2") (pinfunction "2_2") (pintype "passive"))
      (node (ref "U16") (pin "2") (pinfunction "SDA1_2") (pintype "bidirectional"))
    )
    (net (code "25") (name "/SDA_TO_INA") (class "Default")
      (node (ref "R152") (pin "1") (pinfunction "1_1") (pintype "passive"))
      (node (ref "U16") (pin "7") (pinfunction "SDA2_7") (pintype "bidirectional"))
    )
    (net (code "26") (name "/SDOUT") (class "Default")
      (node (ref "U44") (pin "9") (pinfunction "B4_9") (pintype "bidirectional"))
    )
    (net (code "27") (name "/SDOUT_FROM_CPLD") (class "Default")
      (node (ref "U44") (pin "4") (pinfunction "A4_4") (pintype "bidirectional"))
      (node (ref "U6") (pin "11") (pinfunction "IND_11") (pintype "input"))
    )
    (net (code "28") (name "/SDOUT_FTDI") (class "Default")
      (node (ref "U6") (pin "6") (pinfunction "OUTD_6") (pintype "tri_state"))
      (node (ref "U7") (pin "12") (pinfunction "ADBUS0_12") (pintype "bidirectional"))
    )
    (net (code "29") (name "/SEN_CPLD_FTDI") (class "Default")
      (node (ref "U6") (pin "4") (pinfunction "INB_4") (pintype "input"))
      (node (ref "U7") (pin "18") (pinfunction "ADBUS5_18") (pintype "bidirectional"))
    )
    (net (code "30") (name "/SEN_CPLD_TO_CPLD") (class "Default")
      (node (ref "U6") (pin "13") (pinfunction "OUTB_13") (pintype "tri_state"))
    )
    (net (code "31") (name "/SEN_DIRECT") (class "Default")
      (node (ref "U44") (pin "10") (pinfunction "B3_10") (pintype "bidirectional"))
    )
    (net (code "32") (name "/SEN_FTDI") (class "Default")
      (node (ref "U6") (pin "5") (pinfunction "INC_5") (pintype "input"))
      (node (ref "U7") (pin "17") (pinfunction "ADBUS4_17") (pintype "bidirectional"))
    )
    (net (code "33") (name "/SEN_TX7364_TO_CPLD") (class "Default")
      (node (ref "TP14") (pin "1") (pintype "passive"))
      (node (ref "U44") (pin "3") (pinfunction "A3_3") (pintype "bidirectional"))
      (node (ref "U6") (pin "12") (pinfunction "OUTC_12") (pintype "tri_state"))
    )
    (net (code "34") (name "/SP2_FTDI") (class "Default")
      (node (ref "U14") (pin "4") (pinfunction "INB_4") (pintype "input"))
      (node (ref "U7") (pin "51") (pinfunction "DDBUS5_51") (pintype "bidirectional"))
    )
    (net (code "35") (name "/SP2_TO_CPLD") (class "Default")
      (node (ref "U14") (pin "13") (pinfunction "OUTB_13") (pintype "tri_state"))
    )
    (net (code "36") (name "/SP3_FTDI") (class "Default")
      (node (ref "U14") (pin "5") (pinfunction "INC_5") (pintype "input"))
      (node (ref "U7") (pin "52") (pinfunction "DDBUS6_52") (pintype "bidirectional"))
    )
    (net (code "37") (name "/SP3_TO_CPLD") (class "Default")
      (node (ref "U14") (pin "12") (pinfunction "OUTC_12") (pintype "tri_state"))
    )
    (net (code "38") (name "/SP4_FROM_CPLD") (class "Default")
      (node (ref "U14") (pin "11") (pinfunction "IND_11") (pintype "input"))
    )
    (net (code "39") (name "/SP4_FTDI") (class "Default")
      (node (ref "U14") (pin "6") (pinfunction "OUTD_6") (pintype "tri_state"))
      (node (ref "U7") (pin "53") (pinfunction "DDBUS7_53") (pintype "bidirectional"))
    )
    (net (code "40") (name "/TCK_FTDI") (class "Default")
      (node (ref "U17") (pin "3") (pinfunction "INA_3") (pintype "input"))
      (node (ref "U7") (pin "42") (pinfunction "DDBUS0_42") (pintype "bidirectional"))
    )
    (net (code "41") (name "/TCK_TO_CPLD") (class "Default")
      (node (ref "TP6") (pin "1") (pintype "passive"))
      (node (ref "U17") (pin "14") (pinfunction "OUTA_14") (pintype "tri_state"))
    )
    (net (code "42") (name "/TDI_FTDI") (class "Default")
      (node (ref "U17") (pin "4") (pinfunction "INB_4") (pintype "input"))
      (node (ref "U7") (pin "46") (pinfunction "DDBUS1_46") (pintype "bidirectional"))
    )
    (net (code "43") (name "/TDI_TO_CPLD") (class "Default")
      (node (ref "TP7") (pin "1") (pintype "passive"))
      (node (ref "U17") (pin "13") (pinfunction "OUTB_13") (pintype "tri_state"))
    )
    (net (code "44") (name "/TDO_FROM_CPLD") (class "Default")
      (node (ref "TP9") (pin "1") (pintype "passive"))
      (node (ref "U17") (pin "11") (pinfunction "IND_11") (pintype "input"))
    )
    (net (code "45") (name "/TDO_FTDI") (class "Default")
      (node (ref "U17") (pin "6") (pinfunction "OUTD_6") (pintype "tri_state"))
      (node (ref "U7") (pin "47") (pinfunction "DDBUS2_47") (pintype "bidirectional"))
    )
    (net (code "46") (name "/TMS_FTDI") (class "Default")
      (node (ref "U17") (pin "5") (pinfunction "INC_5") (pintype "input"))
      (node (ref "U7") (pin "48") (pinfunction "DDBUS3_48") (pintype "bidirectional"))
    )
    (net (code "47") (name "/TMS_TO_CPLD") (class "Default")
      (node (ref "TP8") (pin "1") (pintype "passive"))
      (node (ref "U17") (pin "12") (pinfunction "OUTC_12") (pintype "tri_state"))
    )
    (net (code "48") (name "/USB_D_N") (class "Default")
      (node (ref "C102") (pin "1") (pinfunction "1_1") (pintype "passive"))
      (node (ref "J9") (pin "2") (pinfunction "D-_2") (pintype "bidirectional"))
      (node (ref "R145") (pin "1") (pinfunction "1_1") (pintype "passive"))
    )
    (net (code "49") (name "/USB_D_P") (class "Default")
      (node (ref "C101") (pin "1") (pinfunction "1_1") (pintype "passive"))
      (node (ref "J9") (pin "3") (pinfunction "D+_3") (pintype "bidirectional"))
      (node (ref "R141") (pin "1") (pinfunction "1_1") (pintype "passive"))
    )
    (net (code "50") (name "/VER0") (class "Default")
      (node (ref "R284") (pin "2") (pinfunction "2_2") (pintype "passive"))
      (node (ref "R286") (pin "1") (pinfunction "1_1") (pintype "passive"))
      (node (ref "U7") (pin "27") (pinfunction "BDBUS5_27") (pintype "bidirectional"))
    )
    (net (code "51") (name "/VER1") (class "Default")
      (node (ref "R283") (pin "2") (pinfunction "2_2") (pintype "passive"))
      (node (ref "R285") (pin "1") (pinfunction "1_1") (pintype "passive"))
      (node (ref "U7") (pin "28") (pinfunction "BDBUS6_28") (pintype "bidirectional"))
    )
    (net (code "52") (name "/V_1P8_CPLD") (class "Default")
      (node (ref "C212") (pin "2") (pinfunction "2_2") (pintype "passive"))
      (node (ref "U44") (pin "13") (pinfunction "VCCB_13") (pintype "power_in"))
    )
    (net (code "53") (name "/V_2P5") (class "Default")
      (node (ref "U14") (pin "10") (pinfunction "EN2_10") (pintype "input"))
      (node (ref "U17") (pin "10") (pinfunction "EN2_10") (pintype "input"))
      (node (ref "U6") (pin "10") (pinfunction "EN2_10") (pintype "input"))
      (node (ref "U8") (pin "10") (pinfunction "EN2_10") (pintype "input"))
    )
    (net (code "54") (name "/V_2P5_CPLD") (class "Default")
      (node (ref "C100") (pin "1") (pinfunction "1_1") (pintype "passive"))
      (node (ref "C107") (pin "1") (pinfunction "1_1") (pintype "passive"))
      (node (ref "C149") (pin "1") (pinfunction "1_1") (pintype "passive"))
      (node (ref "C211") (pin "2") (pinfunction "2_2") (pintype "passive"))
      (node (ref "C36") (pin "1") (pinfunction "1_1") (pintype "passive"))
      (node (ref "U14") (pin "16") (pinfunction "VCC2_16") (pintype "power_in"))
      (node (ref "U17") (pin "16") (pinfunction "VCC2_16") (pintype "power_in"))
      (node (ref "U44") (pin "14") (pinfunction "VCCA_14") (pintype "power_in"))
      (node (ref "U44") (pin "15") (pinfunction "DIR1_15") (pintype "input"))
      (node (ref "U44") (pin "16") (pinfunction "DIR2_16") (pintype "input"))
      (node (ref "U44") (pin "5") (pinfunction "DIR3_5") (pintype "input"))
      (node (ref "U6") (pin "16") (pinfunction "VCC2_16") (pintype "power_in"))
      (node (ref "U8") (pin "16") (pinfunction "VCC2_16") (pintype "power_in"))
    )
    (net (code "55") (name "3P3V_FTDI") (class "Default")
      (node (ref "C105") (pin "1") (pinfunction "1_1") (pintype "passive"))
      (node (ref "C106") (pin "1") (pinfunction "1_1") (pintype "passive"))
      (node (ref "C120") (pin "1") (pinfunction "1_1") (pintype "passive"))
      (node (ref "C126") (pin "1") (pinfunction "1_1") (pintype "passive"))
      (node (ref "C127") (pin "1") (pinfunction "1_1") (pintype "passive"))
      (node (ref "C128") (pin "1") (pinfunction "1_1") (pintype "passive"))
      (node (ref "C129") (pin "1") (pinfunction "1_1") (pintype "passive"))
      (node (ref "C150") (pin "1") (pinfunction "1_1") (pintype "passive"))
      (node (ref "C250") (pin "1") (pinfunction "1_1") (pintype "passive"))
      (node (ref "C30") (pin "1") (pinfunction "1_1") (pintype "passive"))
      (node (ref "C31") (pin "1") (pinfunction "1_1") (pintype "passive"))
      (node (ref "C32") (pin "1") (pinfunction "1_1") (pintype "passive"))
      (node (ref "C35") (pin "1") (pinfunction "1_1") (pintype "passive"))
      (node (ref "C37") (pin "1") (pinfunction "1_1") (pintype "passive"))
      (node (ref "C49") (pin "1") (pinfunction "1_1") (pintype "passive"))
      (node (ref "C99") (pin "1") (pinfunction "1_1") (pintype "passive"))
      (node (ref "D17") (pin "1") (pinfunction "A_1") (pintype "passive"))
      (node (ref "R130") (pin "1") (pinfunction "1_1") (pintype "passive"))
      (node (ref "R135") (pin "2") (pinfunction "2_2") (pintype "passive"))
      (node (ref "R156") (pin "1") (pinfunction "1_1") (pintype "passive"))
      (node (ref "R157") (pin "1") (pinfunction "1_1") (pintype "passive"))
      (node (ref "R158") (pin "1") (pinfunction "1_1") (pintype "passive"))
      (node (ref "R161") (pin "1") (pinfunction "1_1") (pintype "passive"))
      (node (ref "R162") (pin "1") (pinfunction "1_1") (pintype "passive"))
      (node (ref "R283") (pin "1") (pinfunction "1_1") (pintype "passive"))
      (node (ref "R284") (pin "1") (pinfunction "1_1") (pintype "passive"))
      (node (ref "TP43") (pin "1") (pintype "passive"))
      (node (ref "U10") (pin "8") (pinfunction "VCC_8") (pintype "power_in"))
      (node (ref "U14") (pin "1") (pinfunction "VCC1_1") (pintype "power_in"))
      (node (ref "U14") (pin "7") (pinfunction "EN1_7") (pintype "input"))
      (node (ref "U15") (pin "5") (pinfunction "OUT_5") (pintype "power_in"))
      (node (ref "U16") (pin "1") (pinfunction "VCC1_1") (pintype "power_in"))
      (node (ref "U17") (pin "1") (pinfunction "VCC1_1") (pintype "power_in"))
      (node (ref "U17") (pin "7") (pinfunction "EN1_7") (pintype "input"))
      (node (ref "U6") (pin "1") (pinfunction "VCC1_1") (pintype "power_in"))
      (node (ref "U6") (pin "7") (pinfunction "EN1_7") (pintype "input"))
      (node (ref "U7") (pin "16") (pinfunction "VCCIO_16") (pintype "power_in"))
      (node (ref "U7") (pin "36") (pinfunction "VCCIO_36") (pintype "power_in"))
      (node (ref "U7") (pin "44") (pinfunction "VREGIN_44") (pintype "power_in"))
      (node (ref "U7") (pin "5") (pinfunction "VPHY_5") (pintype "power_in"))
      (node (ref "U7") (pin "50") (pinfunction "VCCIO_50") (pintype "power_in"))
      (node (ref "U7") (pin "9") (pinfunction "VPLL_9") (pintype "power_in"))
      (node (ref "U8") (pin "1") (pinfunction "VCC1_1") (pintype "power_in"))
    )
    (net (code "56") (name "GND") (class "Default")
      (node (ref "C100") (pin "2") (pinfunction "2_2") (pintype "passive"))
      (node (ref "C107") (pin "2") (pinfunction "2_2") (pintype "passive"))
      (node (ref "C149") (pin "2") (pinfunction "2_2") (pintype "passive"))
      (node (ref "C161") (pin "2") (pinfunction "2_2") (pintype "passive"))
      (node (ref "C211") (pin "1") (pinfunction "1_1") (pintype "passive"))
      (node (ref "C212") (pin "1") (pinfunction "1_1") (pintype "passive"))
      (node (ref "C36") (pin "2") (pinfunction "2_2") (pintype "passive"))
      (node (ref "U14") (pin "15") (pinfunction "GND2_15") (pintype "power_in"))
      (node (ref "U14") (pin "9") (pinfunction "GND2_9") (pintype "power_in"))
      (node (ref "U16") (pin "5") (pinfunction "GND2_5") (pintype "power_in"))
      (node (ref "U17") (pin "15") (pinfunction "GND2_15") (pintype "power_in"))
      (node (ref "U17") (pin "9") (pinfunction "GND2_9") (pintype "power_in"))
      (node (ref "U44") (pin "6") (pinfunction "DIR4_6") (pintype "input"))
      (node (ref "U44") (pin "7") (pinfunction "OE_7") (pintype "input"))
      (node (ref "U44") (pin "8") (pinfunction "GND_8") (pintype "power_in"))
      (node (ref "U6") (pin "15") (pinfunction "GND2_15") (pintype "power_in"))
      (node (ref "U6") (pin "9") (pinfunction "GND2_9") (pintype "power_in"))
      (node (ref "U8") (pin "15") (pinfunction "GND2_15") (pintype "power_in"))
      (node (ref "U8") (pin "9") (pinfunction "GND2_9") (pintype "power_in"))
    )
    (net (code "57") (name "Net-(D13-K)") (class "Default")
      (node (ref "D13") (pin "2") (pinfunction "K_2") (pintype "passive"))
      (node (ref "R110") (pin "1") (pinfunction "1_1") (pintype "passive"))
    )
    (net (code "58") (name "Net-(D17-K)") (class "Default")
      (node (ref "D17") (pin "2") (pinfunction "K_2") (pintype "passive"))
      (node (ref "R124") (pin "1") (pinfunction "1_1") (pintype "passive"))
    )
    (net (code "59") (name "Net-(J9-VBUS)") (class "Default")
      (node (ref "FB1") (pin "1") (pinfunction "1_1") (pintype "passive"))
      (node (ref "J9") (pin "1") (pinfunction "VBUS_1") (pintype "passive"))
    )
    (net (code "60") (name "Net-(U7-BDBUS1)") (class "Default")
      (node (ref "R30") (pin "1") (pinfunction "1_1") (pintype "passive"))
      (node (ref "U7") (pin "23") (pinfunction "BDBUS1_23") (pintype "bidirectional"))
    )
    (net (code "61") (name "Net-(U7-BDBUS2)") (class "Default")
      (node (ref "R137") (pin "1") (pinfunction "1_1") (pintype "passive"))
      (node (ref "U7") (pin "24") (pinfunction "BDBUS2_24") (pintype "bidirectional"))
    )
    (net (code "62") (name "Net-(U7-OSCI)") (class "Default")
      (node (ref "C140") (pin "1") (pinfunction "1_1") (pintype "passive"))
      (node (ref "U7") (pin "3") (pinfunction "OSCI_3") (pintype "passive"))
      (node (ref "Y2") (pin "2") (pinfunction "OSC2_2") (pintype "passive"))
    )
    (net (code "63") (name "Net-(U7-OSCO)") (class "Default")
      (node (ref "C141") (pin "1") (pinfunction "1_1") (pintype "passive"))
      (node (ref "U7") (pin "4") (pinfunction "OSCO_4") (pintype "passive"))
      (node (ref "Y2") (pin "1") (pinfunction "OSC1_1") (pintype "passive"))
    )
    (net (code "64") (name "Net-(U7-REF)") (class "Default")
      (node (ref "R129") (pin "2") (pinfunction "2_2") (pintype "passive"))
      (node (ref "U7") (pin "6") (pinfunction "REF_6") (pintype "input"))
    )
    (net (code "65") (name "Net-(U7-RESET)") (class "Default")
      (node (ref "R130") (pin "2") (pinfunction "2_2") (pintype "passive"))
      (node (ref "U7") (pin "11") (pinfunction "RESET_11") (pintype "input"))
    )
    (net (code "66") (name "Net-(U10-DO)") (class "Default")
      (node (ref "R134") (pin "2") (pinfunction "2_2") (pintype "passive"))
      (node (ref "U10") (pin "4") (pinfunction "DO_4") (pintype "tri_state"))
    )
    (net (code "67") (name "Net-(U15-FB)") (class "Default")
      (node (ref "C37") (pin "2") (pinfunction "2_2") (pintype "passive"))
      (node (ref "R135") (pin "1") (pinfunction "1_1") (pintype "passive"))
      (node (ref "R136") (pin "2") (pinfunction "2_2") (pintype "passive"))
      (node (ref "U15") (pin "4") (pinfunction "FB_4") (pintype "input"))
    )
    (net (code "68") (name "USB_GND") (class "Default")
      (node (ref "C101") (pin "2") (pinfunction "2_2") (pintype "passive"))
      (node (ref "C102") (pin "2") (pinfunction "2_2") (pintype "passive"))
      (node (ref "C103") (pin "2") (pinfunction "2_2") (pintype "passive"))
      (node (ref "C104") (pin "2") (pinfunction "2_2") (pintype "passive"))
      (node (ref "C105") (pin "2") (pinfunction "2_2") (pintype "passive"))
      (node (ref "C106") (pin "2") (pinfunction "2_2") (pintype "passive"))
      (node (ref "C120") (pin "2") (pinfunction "2_2") (pintype "passive"))
      (node (ref "C126") (pin "2") (pinfunction "2_2") (pintype "passive"))
      (node (ref "C127") (pin "2") (pinfunction "2_2") (pintype "passive"))
      (node (ref "C128") (pin "2") (pinfunction "2_2") (pintype "passive"))
      (node (ref "C129") (pin "2") (pinfunction "2_2") (pintype "passive"))
      (node (ref "C140") (pin "2") (pinfunction "2_2") (pintype "passive"))
      (node (ref "C141") (pin "2") (pinfunction "2_2") (pintype "passive"))
      (node (ref "C150") (pin "2") (pinfunction "2_2") (pintype "passive"))
      (node (ref "C250") (pin "2") (pinfunction "2_2") (pintype "passive"))
      (node (ref "C30") (pin "2") (pinfunction "2_2") (pintype "passive"))
      (node (ref "C31") (pin "2") (pinfunction "2_2") (pintype "passive"))
      (node (ref "C32") (pin "2") (pinfunction "2_2") (pintype "passive"))
      (node (ref "C33") (pin "1") (pinfunction "1_1") (pintype "passive"))
      (node (ref "C35") (pin "2") (pinfunction "2_2") (pintype "passive"))
      (node (ref "C46") (pin "2") (pinfunction "2_2") (pintype "passive"))
      (node (ref "C49") (pin "2") (pinfunction "2_2") (pintype "passive"))
      (node (ref "C50") (pin "2") (pinfunction "2_2") (pintype "passive"))
      (node (ref "C53") (pin "2") (pinfunction "2_2") (pintype "passive"))
      (node (ref "C99") (pin "2") (pinfunction "2_2") (pintype "passive"))
      (node (ref "J9") (pin "5") (pinfunction "GND_5") (pintype "passive"))
      (node (ref "J9") (pin "6") (pinfunction "6_6") (pintype "passive"))
      (node (ref "J9") (pin "7") (pinfunction "7_7") (pintype "passive"))
      (node (ref "J9") (pin "8") (pinfunction "8_8") (pintype "power_in"))
      (node (ref "J9") (pin "9") (pinfunction "9_9") (pintype "power_in"))
      (node (ref "R110") (pin "2") (pinfunction "2_2") (pintype "passive"))
      (node (ref "R124") (pin "2") (pinfunction "2_2") (pintype "passive"))
      (node (ref "R129") (pin "1") (pinfunction "1_1") (pintype "passive"))
      (node (ref "R136") (pin "1") (pinfunction "1_1") (pintype "passive"))
      (node (ref "R285") (pin "2") (pinfunction "2_2") (pintype "passive"))
      (node (ref "R286") (pin "2") (pinfunction "2_2") (pintype "passive"))
      (node (ref "U10") (pin "5") (pinfunction "VSS_5") (pintype "power_in"))
      (node (ref "U10") (pin "6") (pinfunction "NC_6") (pintype "passive"))
      (node (ref "U10") (pin "7") (pinfunction "NC_7") (pintype "passive"))
      (node (ref "U14") (pin "2") (pinfunction "GND1_2") (pintype "power_in"))
      (node (ref "U14") (pin "8") (pinfunction "GND1_8") (pintype "power_in"))
      (node (ref "U15") (pin "2") (pinfunction "GND_2") (pintype "power_in"))
      (node (ref "U16") (pin "4") (pinfunction "GND1_4") (pintype "power_in"))
      (node (ref "U17") (pin "2") (pinfunction "GND1_2") (pintype "power_in"))
      (node (ref "U17") (pin "8") (pinfunction "GND1_8") (pintype "power_in"))
      (node (ref "U6") (pin "2") (pinfunction "GND1_2") (pintype "power_in"))
      (node (ref "U6") (pin "8") (pinfunction "GND1_8") (pintype "power_in"))
      (node (ref "U7") (pin "10") (pinfunction "TEST_10") (pintype "input"))
      (node (ref "U7") (pin "21") (pinfunction "GND_21") (pintype "power_in"))
      (node (ref "U7") (pin "41") (pinfunction "GND_41") (pintype "power_in"))
      (node (ref "U7") (pin "45") (pinfunction "GND_45") (pintype "power_in"))
      (node (ref "U7") (pin "57") (pinfunction "PAD_57") (pintype "passive"))
      (node (ref "U8") (pin "2") (pinfunction "GND1_2") (pintype "power_in"))
      (node (ref "U8") (pin "8") (pinfunction "GND1_8") (pintype "power_in"))
    )
    (net (code "69") (name "V_3P3") (class "Default")
      (node (ref "C161") (pin "1") (pinfunction "1_1") (pintype "passive"))
      (node (ref "R152") (pin "2") (pinfunction "2_2") (pintype "passive"))
      (node (ref "R154") (pin "2") (pinfunction "2_2") (pintype "passive"))
      (node (ref "U16") (pin "8") (pinfunction "VCC2_8") (pintype "power_in"))
    )
    (net (code "70") (name "unconnected-(J9-ID-Pad4)") (class "Default")
      (node (ref "J9") (pin "4") (pinfunction "ID_4") (pintype "bidirectional+no_connect"))
    )
    (net (code "71") (name "unconnected-(U7-BDBUS3-Pad25)") (class "Default")
      (node (ref "U7") (pin "25") (pinfunction "BDBUS3_25") (pintype "bidirectional"))
    )
    (net (code "72") (name "unconnected-(U7-BDBUS4-Pad26)") (class "Default")
      (node (ref "U7") (pin "26") (pinfunction "BDBUS4_26") (pintype "bidirectional"))
    )
    (net (code "73") (name "unconnected-(U7-BDBUS7-Pad29)") (class "Default")
      (node (ref "U7") (pin "29") (pinfunction "BDBUS7_29") (pintype "bidirectional"))
    )
    (net (code "74") (name "unconnected-(U7-CDBUS0-Pad32)") (class "Default")
      (node (ref "U7") (pin "32") (pinfunction "CDBUS0_32") (pintype "bidirectional+no_connect"))
    )
    (net (code "75") (name "unconnected-(U7-CDBUS1-Pad33)") (class "Default")
      (node (ref "U7") (pin "33") (pinfunction "CDBUS1_33") (pintype "bidirectional+no_connect"))
    )
    (net (code "76") (name "unconnected-(U7-CDBUS2-Pad34)") (class "Default")
      (node (ref "U7") (pin "34") (pinfunction "CDBUS2_34") (pintype "bidirectional+no_connect"))
    )
    (net (code "77") (name "unconnected-(U7-CDBUS3-Pad35)") (class "Default")
      (node (ref "U7") (pin "35") (pinfunction "CDBUS3_35") (pintype "bidirectional+no_connect"))
    )
    (net (code "78") (name "unconnected-(U7-CDBUS4-Pad37)") (class "Default")
      (node (ref "U7") (pin "37") (pinfunction "CDBUS4_37") (pintype "bidirectional+no_connect"))
    )
    (net (code "79") (name "unconnected-(U7-CDBUS5-Pad38)") (class "Default")
      (node (ref "U7") (pin "38") (pinfunction "CDBUS5_38") (pintype "bidirectional+no_connect"))
    )
    (net (code "80") (name "unconnected-(U7-CDBUS6-Pad39)") (class "Default")
      (node (ref "U7") (pin "39") (pinfunction "CDBUS6_39") (pintype "bidirectional+no_connect"))
    )
    (net (code "81") (name "unconnected-(U7-CDBUS7-Pad40)") (class "Default")
      (node (ref "U7") (pin "40") (pinfunction "CDBUS7_40") (pintype "bidirectional+no_connect"))
    )
    (net (code "82") (name "unconnected-(U7-PWREN-Pad54)") (class "Default")
      (node (ref "U7") (pin "54") (pinfunction "PWREN_54") (pintype "output+no_connect"))
    )
    (net (code "83") (name "unconnected-(U7-SUSPEND-Pad30)") (class "Default")
      (node (ref "U7") (pin "30") (pinfunction "SUSPEND_30") (pintype "output+no_connect"))
    )
    (net (code "84") (name "unconnected-(U8-NC-Pad7)") (class "Default")
      (node (ref "U8") (pin "7") (pinfunction "NC_7") (pintype "passive+no_connect"))
    )
  )
)
